# PCB_TX.net
KiCad netlist of a schematic drawn in Altium Designer
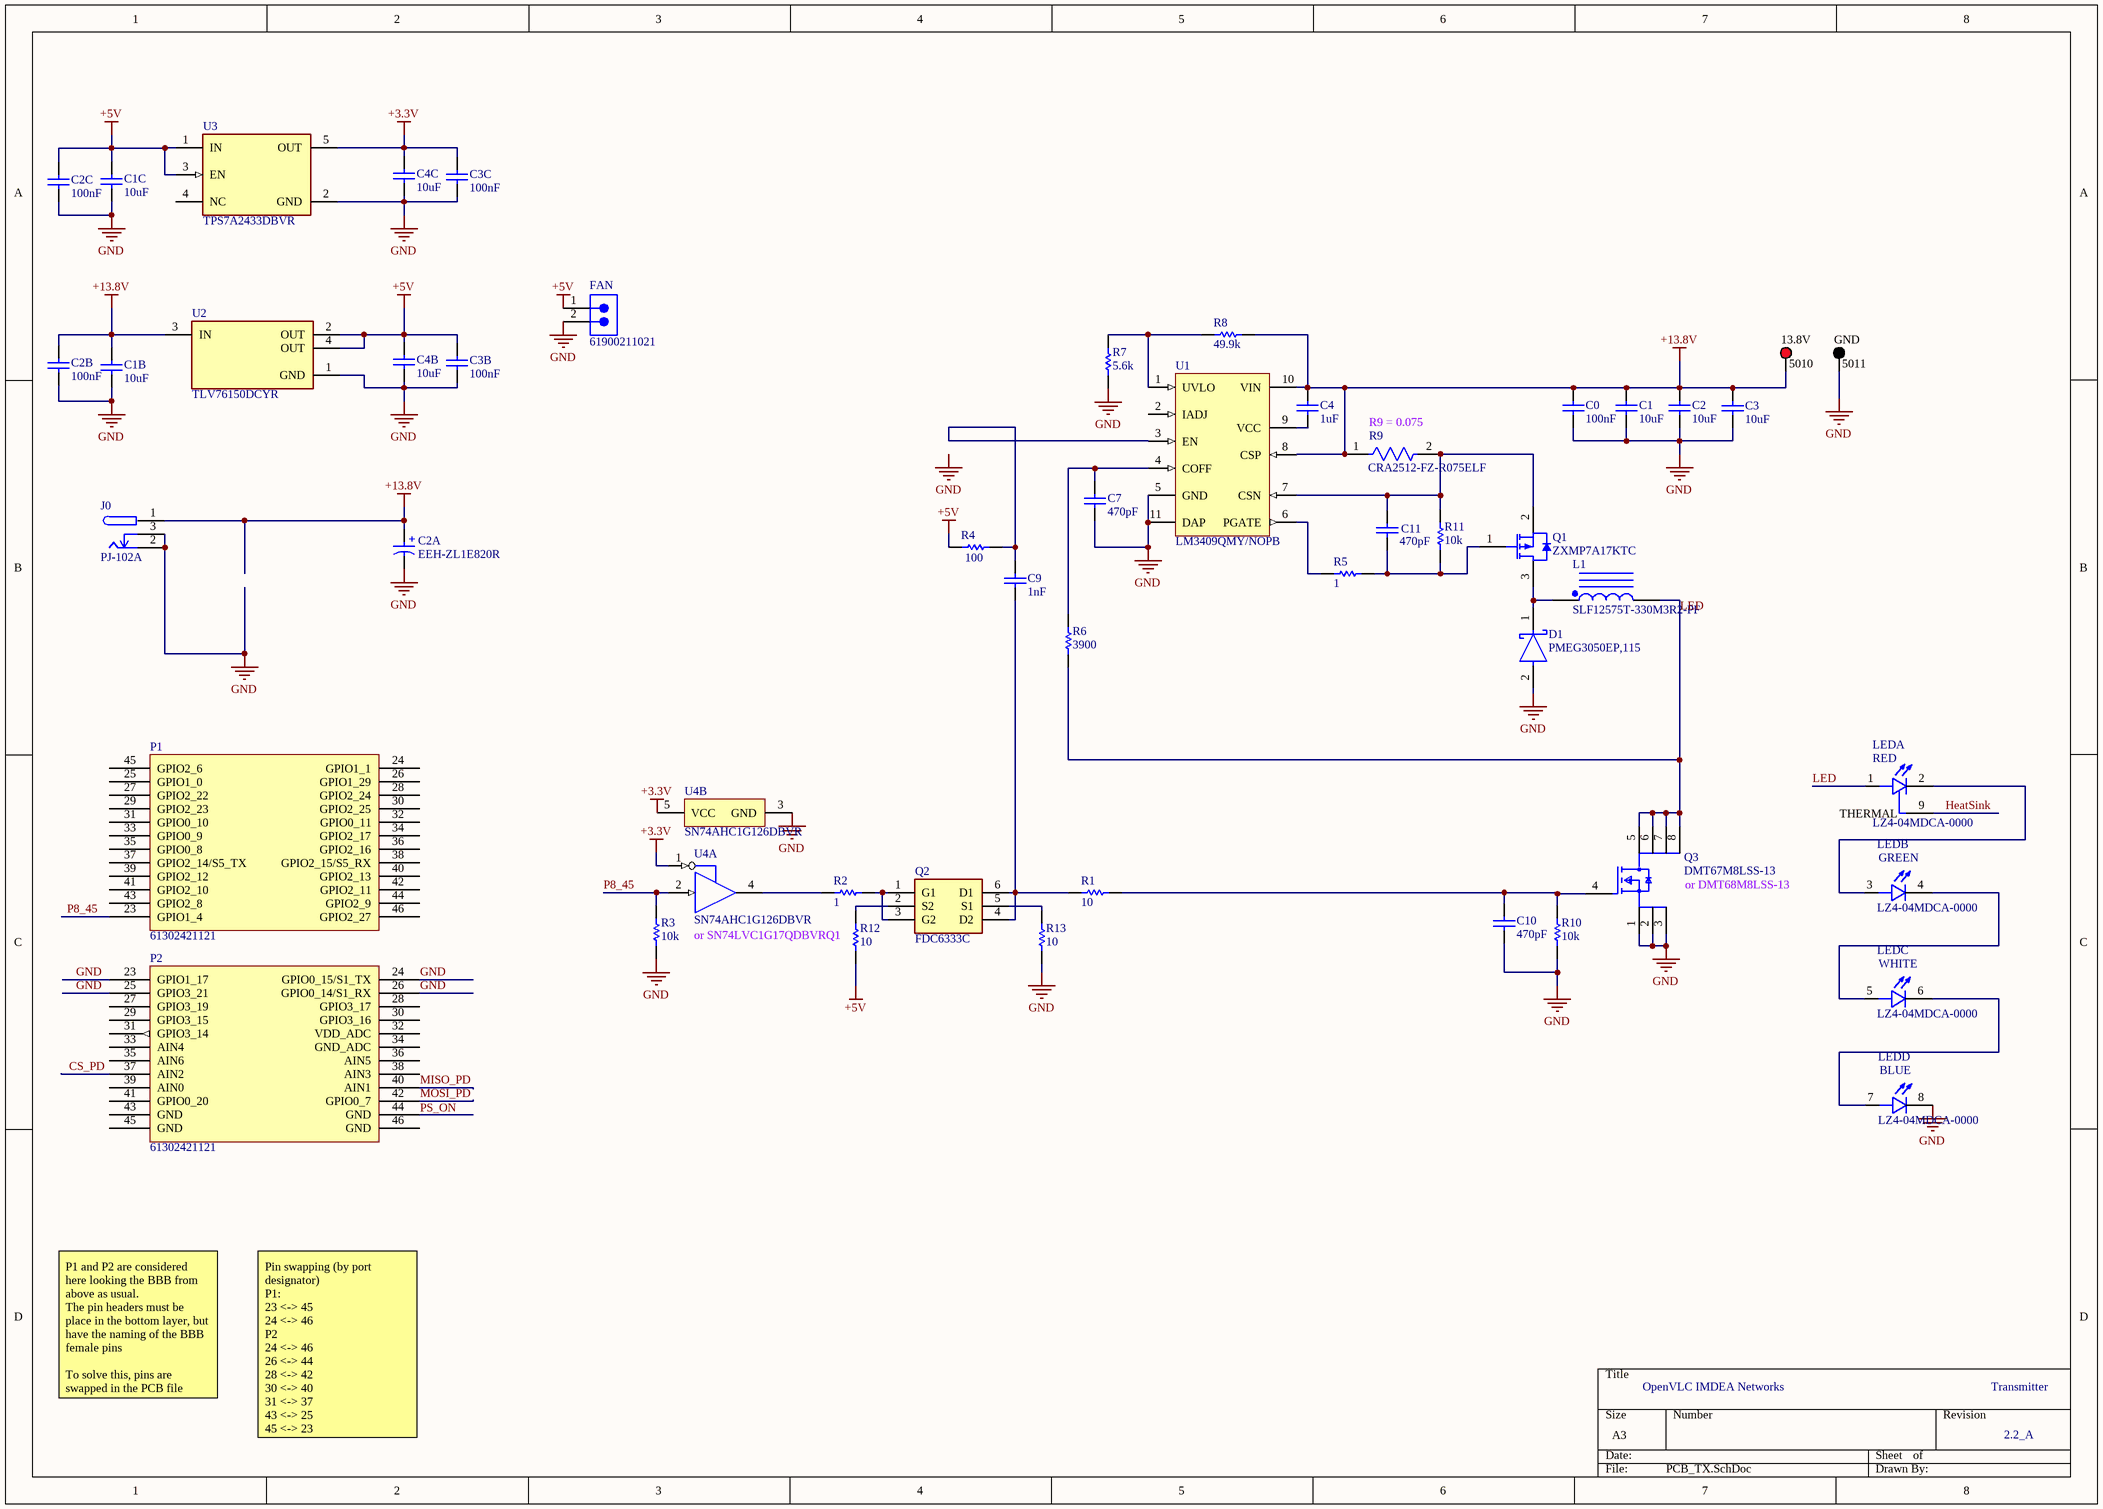
[diagram p0: PCB_TX.SchDoc]

(export (version "E")
  (design (tool "Eeschema 10.0.6"))
  (components
    (comp (ref "13.8V")
      (value "5010")
      (footprint "KSTN-5010_V")
      (description "Test Point, Red, Through Hole, RoHS, Bulk")
      (fields (field (name "MANUFACTURER") "Keystone"))
      (libsource (lib "Altium Content Vault") (part "TESTPOINT_RED"))
    )
    (comp (ref "C0")
      (value "100nF")
      (footprint "RESC1608X55N")
      (description "Capacitor")
      (fields (field (name "Comment") "GCM188R71H104KA57J") (field (name "PUBLISHER") "Altium Limited"))
      (libsource (lib "Miscellaneous Devices") (part "Cap"))
    )
    (comp (ref "C1")
      (value "10uF")
      (footprint "RESC1608X55N")
      (description "Capacitor")
      (fields (field (name "Comment") "GRM188R6YA106MA73D") (field (name "PUBLISHER") "Altium Limited"))
      (libsource (lib "Miscellaneous Devices") (part "Cap"))
    )
    (comp (ref "C1B")
      (value "10uF")
      (footprint "RESC1608X55N")
      (description "Capacitor")
      (fields (field (name "Comment") "GRM188R6YA475KE15D") (field (name "PUBLISHER") "Altium Limited"))
      (libsource (lib "Miscellaneous Devices") (part "Cap"))
    )
    (comp (ref "C1C")
      (value "10uF")
      (footprint "RESC1608X55N")
      (description "Capacitor")
      (fields (field (name "Comment") "GRM188R6YA475KE15D") (field (name "PUBLISHER") "Altium Limited"))
      (libsource (lib "Miscellaneous Devices") (part "Cap"))
    )
    (comp (ref "C2")
      (value "10uF")
      (footprint "RESC1608X55N")
      (description "Capacitor")
      (fields (field (name "Comment") "GRM188R6YA106MA73D") (field (name "PUBLISHER") "Altium Limited"))
      (libsource (lib "Miscellaneous Devices") (part "Cap"))
    )
    (comp (ref "C2A")
      (value "EEH-ZL1E820R")
      (footprint "WCAP-PSLP_D5H5.5")
      (description "875105242006 WCAP-PSLP Aluminum Polymer Capacitors")
      (fields (field (name "TOLERANCE") "20%"))
      (libsource (lib "Altium Content Vault") (part "Capacitor_Polarized"))
    )
    (comp (ref "C2B")
      (value "100nF")
      (footprint "RESC1608X55N")
      (description "Capacitor")
      (fields (field (name "Comment") "GRM188R6YA106MA73D") (field (name "PUBLISHER") "Altium Limited"))
      (libsource (lib "Miscellaneous Devices") (part "Cap"))
    )
    (comp (ref "C2C")
      (value "100nF")
      (footprint "RESC1608X55N")
      (description "Capacitor")
      (fields (field (name "Comment") "GRM188R6YA106MA73D") (field (name "PUBLISHER") "Altium Limited"))
      (libsource (lib "Miscellaneous Devices") (part "Cap"))
    )
    (comp (ref "C3")
      (value "10uF")
      (footprint "RESC1608X55N")
      (description "Capacitor")
      (fields (field (name "Comment") "GRM188R6YA106MA73D") (field (name "PUBLISHER") "Altium Limited"))
      (libsource (lib "Miscellaneous Devices") (part "Cap"))
    )
    (comp (ref "C3B")
      (value "100nF")
      (footprint "RESC1608X55N")
      (description "Capacitor")
      (fields (field (name "Comment") "GCM188R71H104KA57J") (field (name "PUBLISHER") "Altium Limited"))
      (libsource (lib "Miscellaneous Devices") (part "Cap"))
    )
    (comp (ref "C3C")
      (value "100nF")
      (footprint "RESC1608X55N")
      (description "Capacitor")
      (fields (field (name "Comment") "GCM188R71H104KA57J") (field (name "PUBLISHER") "Altium Limited"))
      (libsource (lib "Miscellaneous Devices") (part "Cap"))
    )
    (comp (ref "C4")
      (value "1uF")
      (footprint "RESC1608X55N")
      (description "Capacitor")
      (fields (field (name "Comment") "GCM188D71H105KE36J") (field (name "PUBLISHER") "Altium Limited"))
      (libsource (lib "Miscellaneous Devices") (part "Cap"))
    )
    (comp (ref "C4B")
      (value "10uF")
      (footprint "RESC1608X55N")
      (description "Capacitor")
      (fields (field (name "Comment") "GRM188R6YA106MA73D") (field (name "PUBLISHER") "Altium Limited"))
      (libsource (lib "Miscellaneous Devices") (part "Cap"))
    )
    (comp (ref "C4C")
      (value "10uF")
      (footprint "RESC1608X55N")
      (description "Capacitor")
      (fields (field (name "Comment") "GRM188R6YA106MA73D") (field (name "PUBLISHER") "Altium Limited"))
      (libsource (lib "Miscellaneous Devices") (part "Cap"))
    )
    (comp (ref "C7")
      (value "470pF")
      (footprint "RESC1608X55N")
      (description "Capacitor")
      (fields (field (name "Comment") "GCM1885C1H471JA16D") (field (name "PUBLISHER") "Altium Limited"))
      (libsource (lib "Miscellaneous Devices") (part "Cap"))
    )
    (comp (ref "C9")
      (value "1nF")
      (footprint "RESC1608X55N")
      (description "Capacitor")
      (fields (field (name "Comment") "GRM1885C1H102JA01D") (field (name "PUBLISHER") "Altium Limited"))
      (libsource (lib "Miscellaneous Devices") (part "Cap"))
    )
    (comp (ref "C10")
      (value "470pF")
      (footprint "RESC1608X55N")
      (description "Capacitor")
      (fields (field (name "Comment") "GCM1885C1H471JA16D") (field (name "PUBLISHER") "Altium Limited"))
      (libsource (lib "Miscellaneous Devices") (part "Cap"))
    )
    (comp (ref "C11")
      (value "470pF")
      (footprint "RESC1608X55N")
      (description "Capacitor")
      (fields (field (name "Comment") "GCM1885C1H471JA16D") (field (name "PUBLISHER") "Altium Limited"))
      (libsource (lib "Miscellaneous Devices") (part "Cap"))
    )
    (comp (ref "D1")
      (value "PMEG3050EP,115")
      (footprint "FP-SOD128-MFG")
      (description "DIODE SCHOTTKY 30V 5A SOD128")
      (libsource (lib "Altium Content Vault") (part "1d6ec82d83fb6aee721767c19dac4b9"))
    )
    (comp (ref "FAN")
      (value "61900211021")
      (footprint "61900211021")
      (libsource (lib "Altium Content Vault") (part "Header_Male_1R_02P"))
    )
    (comp (ref "GND")
      (value "5011")
      (footprint "KSTN-5011_V")
      (description "Test Point, Black, Through Hole, RoHS, Bulk")
      (fields (field (name "MANUFACTURER") "Keystone"))
      (libsource (lib "Altium Content Vault") (part "TESTPOINT_BLACK"))
    )
    (comp (ref "J0")
      (value "PJ-102A")
      (footprint "FP-PJ-102A-MFG")
      (description "PJ-102A 2.0 x 6.5 mm, 2.5 A, Horizontal, Through Hole, Tapered Pins, Dc Power Jack Connector")
      (libsource (lib "Altium Content Vault") (part "c639f672d24b5d70918fa8d934b95d1"))
    )
    (comp (ref "L1")
      (value "SLF12575T-330M3R2-PF")
      (footprint "EATN-DR125_V")
      (fields (field (name "MANUFACTURER") "EATON"))
      (libsource (lib "Altium Content Vault") (part "IND-DOT-2"))
    )
    (comp (ref "LED")
      (value "LZ4-04MDCA-0000")
      (footprint "LED_LZ4-04MDCA-0000")
      (fields (field (name "MF") "LED Engin"))
      (libsource (lib "LZ4-04MDCA-0000") (part "LZ4-04MDCA-0000"))
    )
    (comp (ref "P1")
      (value "61302421121")
      (footprint "BBB_CAPE_NO_HEADER_R_24")
      (libsource (lib "BeagleBoneCape") (part "BBB_P8_reduced"))
    )
    (comp (ref "P2")
      (value "61302421121")
      (footprint "BBB_CAPE_NO_HEADER_R_24")
      (libsource (lib "BeagleBoneCape") (part "BBB_P9_reduced"))
    )
    (comp (ref "Q1")
      (value "ZXMP7A17KTC")
      (footprint "DIOD-TO252-3_V")
      (fields (field (name "MANUFACTURER") "Diodes Inc"))
      (libsource (lib "Altium Content Vault") (part "PEMOS-GSD-3"))
    )
    (comp (ref "Q2")
      (value "FDC6333C")
      (footprint "SOT95P275X110-6N")
      (fields (field (name "MOUSER PART NUMBER") "512-FDC6333C"))
      (libsource (lib "FDC6333C") (part "FDC6333C"))
    )
    (comp (ref "Q3")
      (value "DMT67M8LSS-13")
      (footprint "FP-751EB-MFG")
      (description "FDS2672-F085 Trans MOSFET N-CH 200V 3.9A Automotive 8-Pin SOIC T/R")
      (libsource (lib "Altium Content Vault") (part "a2191056e8335feadc5ee6660ea8eee"))
    )
    (comp (ref "R1")
      (value "10")
      (footprint "RESC1608X55N")
      (description "Resistor")
      (fields (field (name "Comment") "RT0603BRD0710RL") (field (name "PUBLISHER") "Altium Limited"))
      (libsource (lib "Miscellaneous Devices") (part "Res1"))
    )
    (comp (ref "R2")
      (value "1")
      (footprint "RESC1608X55N")
      (description "Resistor")
      (fields (field (name "Comment") "RT0603BRD071RL") (field (name "PUBLISHER") "Altium Limited"))
      (libsource (lib "Miscellaneous Devices") (part "Res1"))
    )
    (comp (ref "R3")
      (value "10k")
      (footprint "RESC1608X55N")
      (description "Resistor")
      (fields (field (name "Comment") "RT0603BRD0710KL") (field (name "PUBLISHER") "Altium Limited"))
      (libsource (lib "Miscellaneous Devices") (part "Res1"))
    )
    (comp (ref "R4")
      (value "100")
      (footprint "RESC1608X55N")
      (description "Resistor")
      (fields (field (name "Comment") "RT0603BRD07100RL") (field (name "PUBLISHER") "Altium Limited"))
      (libsource (lib "Miscellaneous Devices") (part "Res1"))
    )
    (comp (ref "R5")
      (value "1")
      (footprint "RESC1608X55N")
      (description "Resistor")
      (fields (field (name "Comment") "RT0603BRD0710RL") (field (name "PUBLISHER") "Altium Limited"))
      (libsource (lib "Miscellaneous Devices") (part "Res1"))
    )
    (comp (ref "R6")
      (value "3900")
      (footprint "RESC1608X55N")
      (description "Resistor")
      (fields (field (name "Comment") "RT0603BRD073K9L") (field (name "PUBLISHER") "Altium Limited"))
      (libsource (lib "Miscellaneous Devices") (part "Res1"))
    )
    (comp (ref "R7")
      (value "5.6k")
      (footprint "RESC1608X55N")
      (description "Resistor")
      (fields (field (name "Comment") "RT0603BRD075K76L") (field (name "PUBLISHER") "Altium Limited"))
      (libsource (lib "Miscellaneous Devices") (part "Res1"))
    )
    (comp (ref "R8")
      (value "49.9k")
      (footprint "RESC1608X55N")
      (description "Resistor")
      (fields (field (name "Comment") "RT0603BRD0749K9L") (field (name "PUBLISHER") "Altium Limited"))
      (libsource (lib "Miscellaneous Devices") (part "Res1"))
    )
    (comp (ref "R9")
      (value "CRA2512-FZ-R075ELF")
      (footprint "FP-CSRN2512-IPC_B")
      (description "Res Thick Film 2512 0.1Ω 1% 2W ±200ppm/°C Molded SMD Plastic T/R")
      (fields (field (name "TOLERANCE") "1%"))
      (libsource (lib "Altium Content Vault") (part "1029c3af85768c4190bb7ad29bc67b5"))
    )
    (comp (ref "R10")
      (value "10k")
      (footprint "RESC1608X55N")
      (description "Resistor")
      (fields (field (name "Comment") "RT0603BRD0710KL") (field (name "PUBLISHER") "Altium Limited"))
      (libsource (lib "Miscellaneous Devices") (part "Res1"))
    )
    (comp (ref "R11")
      (value "10k")
      (footprint "RESC1608X55N")
      (description "Resistor")
      (fields (field (name "Comment") "RT0603BRD0710KL") (field (name "PUBLISHER") "Altium Limited"))
      (libsource (lib "Miscellaneous Devices") (part "Res1"))
    )
    (comp (ref "R12")
      (value "10")
      (footprint "RESC1608X55N")
      (description "Resistor")
      (fields (field (name "Comment") "RT0603BRD0710RL") (field (name "PUBLISHER") "Altium Limited"))
      (libsource (lib "Miscellaneous Devices") (part "Res1"))
    )
    (comp (ref "R13")
      (value "10")
      (footprint "RESC1608X55N")
      (description "Resistor")
      (fields (field (name "Comment") "RT0603BRD0710RL") (field (name "PUBLISHER") "Altium Limited"))
      (libsource (lib "Miscellaneous Devices") (part "Res1"))
    )
    (comp (ref "U1")
      (value "LM3409QMY/NOPB")
      (footprint "DGQ0010A_N")
      (description "PFET Buck Controller for High Power LED Drives, 10-pin eMSOP, Pb-Free")
      (fields (field (name "MANUFACTURER") "Texas Instruments"))
      (libsource (lib "Altium Content Vault") (part "IN-LEDD-LM3409-11"))
    )
    (comp (ref "U2")
      (value "TLV76150DCYR")
      (footprint "FP-DCY0004A-MFG")
      (description "TLV76150DCYR 1-A 16-V high-PSRR linear voltage regulator 4-SOT-223 -40 to 125")
      (libsource (lib "Altium Content Vault") (part "991ffb903c51cf6179ce9942c0606aa"))
    )
    (comp (ref "U3")
      (value "TPS7A2433DBVR")
      (footprint "FP-DBV0005A-MFG")
      (libsource (lib "Altium Content Vault") (part "ee7747973c1ed1d4cccbb20406fa51c"))
    )
    (comp (ref "U4")
      (value "SN74AHC1G126DBVR")
      (footprint "DBV0005A_M")
      (description "Single Bus Buffer Gate With 3-State Outputs, DBV0005A, LARGE T&R")
      (fields
        (field (name "GENERIC PART NUMBER") "SN74AHC1G126")
        (field (name "MANUFACTURER") "Texas Instruments")
      )
      (libsource (lib "Altium Content Vault") (part "TI-SN74XXXXXX126-5"))
    )
  )
  (nets
    (net (code "1") (name "+3.3V") (class "Default")
      (node (ref "C3C") (pin "1") (pinfunction "1_1") (pintype "passive"))
      (node (ref "C4C") (pin "2") (pinfunction "2_2") (pintype "passive"))
      (node (ref "U3") (pin "5") (pinfunction "OUT_5") (pintype "power_in"))
      (node (ref "U4") (pin "1") (pinfunction "OE_1") (pintype "input"))
      (node (ref "U4") (pin "5") (pinfunction "VCC_5") (pintype "power_in"))
    )
    (net (code "2") (name "+5V") (class "Default")
      (node (ref "C1C") (pin "2") (pinfunction "2_2") (pintype "passive"))
      (node (ref "C2C") (pin "1") (pinfunction "1_1") (pintype "passive"))
      (node (ref "C3B") (pin "1") (pinfunction "1_1") (pintype "passive"))
      (node (ref "C4B") (pin "2") (pinfunction "2_2") (pintype "passive"))
      (node (ref "FAN") (pin "1") (pinfunction "1_1") (pintype "passive"))
      (node (ref "R12") (pin "2") (pinfunction "2_2") (pintype "passive"))
      (node (ref "R4") (pin "2") (pinfunction "2_2") (pintype "passive"))
      (node (ref "U2") (pin "2") (pinfunction "OUT_2") (pintype "passive"))
      (node (ref "U2") (pin "4") (pinfunction "OUT_4") (pintype "passive"))
      (node (ref "U3") (pin "1") (pinfunction "IN_1") (pintype "power_in"))
      (node (ref "U3") (pin "3") (pinfunction "EN_3") (pintype "input"))
    )
    (net (code "3") (name "+13.8V") (class "Default")
      (node (ref "13.8V") (pin "1") (pinfunction "1_1") (pintype "passive"))
      (node (ref "C0") (pin "1") (pinfunction "1_1") (pintype "passive"))
      (node (ref "C1") (pin "1") (pinfunction "1_1") (pintype "passive"))
      (node (ref "C1B") (pin "2") (pinfunction "2_2") (pintype "passive"))
      (node (ref "C2") (pin "1") (pinfunction "1_1") (pintype "passive"))
      (node (ref "C2A") (pin "1") (pinfunction "P_1") (pintype "passive"))
      (node (ref "C2B") (pin "1") (pinfunction "1_1") (pintype "passive"))
      (node (ref "C3") (pin "1") (pinfunction "1_1") (pintype "passive"))
      (node (ref "C4") (pin "1") (pinfunction "1_1") (pintype "passive"))
      (node (ref "J0") (pin "1") (pinfunction "1_1") (pintype "passive"))
      (node (ref "R8") (pin "1") (pinfunction "1_1") (pintype "passive"))
      (node (ref "R9") (pin "1") (pinfunction "1_1") (pintype "passive"))
      (node (ref "U1") (pin "10") (pinfunction "VIN_10") (pintype "power_in"))
      (node (ref "U1") (pin "8") (pinfunction "CSP_8") (pintype "input"))
      (node (ref "U2") (pin "3") (pinfunction "IN_3") (pintype "power_in"))
    )
    (net (code "4") (name "/CS_PD") (class "Default")
      (node (ref "P2") (pin "37") (pinfunction "AIN2_37") (pintype "passive"))
    )
    (net (code "5") (name "/HeatSink") (class "Default")
      (node (ref "LED") (pin "9") (pinfunction "THERMAL_9") (pintype "power_in"))
    )
    (net (code "6") (name "/LED") (class "Default")
      (node (ref "L1") (pin "2") (pinfunction "2_2") (pintype "passive"))
      (node (ref "LED") (pin "1") (pinfunction "A_1") (pintype "passive"))
      (node (ref "Q3") (pin "5") (pinfunction "D_5") (pintype "passive"))
      (node (ref "Q3") (pin "6") (pinfunction "D_6") (pintype "passive"))
      (node (ref "Q3") (pin "7") (pinfunction "D_7") (pintype "passive"))
      (node (ref "Q3") (pin "8") (pinfunction "D_8") (pintype "passive"))
      (node (ref "R6") (pin "2") (pinfunction "2_2") (pintype "passive"))
    )
    (net (code "7") (name "/MISO_PD") (class "Default")
      (node (ref "P2") (pin "40") (pinfunction "AIN1_40") (pintype "passive"))
    )
    (net (code "8") (name "/MOSI_PD") (class "Default")
      (node (ref "P2") (pin "42") (pinfunction "GPIO0_7_42") (pintype "passive"))
    )
    (net (code "9") (name "/P8_45") (class "Default")
      (node (ref "P1") (pin "23") (pinfunction "GPIO1_4_23") (pintype "passive"))
      (node (ref "R3") (pin "1") (pinfunction "1_1") (pintype "passive"))
      (node (ref "U4") (pin "2") (pinfunction "A_2") (pintype "input"))
    )
    (net (code "11") (name "GND") (class "Default")
      (node (ref "C0") (pin "2") (pinfunction "2_2") (pintype "passive"))
      (node (ref "C1") (pin "2") (pinfunction "2_2") (pintype "passive"))
      (node (ref "C10") (pin "2") (pinfunction "2_2") (pintype "passive"))
      (node (ref "C1B") (pin "1") (pinfunction "1_1") (pintype "passive"))
      (node (ref "C1C") (pin "1") (pinfunction "1_1") (pintype "passive"))
      (node (ref "C2") (pin "2") (pinfunction "2_2") (pintype "passive"))
      (node (ref "C2A") (pin "2") (pinfunction "N_2") (pintype "passive"))
      (node (ref "C2B") (pin "2") (pinfunction "2_2") (pintype "passive"))
      (node (ref "C2C") (pin "2") (pinfunction "2_2") (pintype "passive"))
      (node (ref "C3") (pin "2") (pinfunction "2_2") (pintype "passive"))
      (node (ref "C3B") (pin "2") (pinfunction "2_2") (pintype "passive"))
      (node (ref "C3C") (pin "2") (pinfunction "2_2") (pintype "passive"))
      (node (ref "C4B") (pin "1") (pinfunction "1_1") (pintype "passive"))
      (node (ref "C4C") (pin "1") (pinfunction "1_1") (pintype "passive"))
      (node (ref "C7") (pin "2") (pinfunction "2_2") (pintype "passive"))
      (node (ref "D1") (pin "2") (pinfunction "A_2") (pintype "passive"))
      (node (ref "FAN") (pin "2") (pinfunction "2_2") (pintype "passive"))
      (node (ref "GND") (pin "1") (pinfunction "1_1") (pintype "passive"))
      (node (ref "J0") (pin "2") (pinfunction "2_2") (pintype "passive"))
      (node (ref "J0") (pin "3") (pinfunction "3_3") (pintype "passive"))
      (node (ref "LED") (pin "8") (pinfunction "C_8") (pintype "passive"))
      (node (ref "P2") (pin "23") (pinfunction "GPIO1_17_23") (pintype "passive"))
      (node (ref "P2") (pin "24") (pinfunction "GPIO0_15/S1_TX_24") (pintype "passive"))
      (node (ref "P2") (pin "25") (pinfunction "GPIO3_21_25") (pintype "passive"))
      (node (ref "P2") (pin "26") (pinfunction "GPIO0_14/S1_RX_26") (pintype "passive"))
      (node (ref "Q3") (pin "1") (pinfunction "S_1") (pintype "passive"))
      (node (ref "Q3") (pin "2") (pinfunction "S_2") (pintype "passive"))
      (node (ref "Q3") (pin "3") (pinfunction "S_3") (pintype "passive"))
      (node (ref "R10") (pin "2") (pinfunction "2_2") (pintype "passive"))
      (node (ref "R13") (pin "2") (pinfunction "2_2") (pintype "passive"))
      (node (ref "R3") (pin "2") (pinfunction "2_2") (pintype "passive"))
      (node (ref "R7") (pin "2") (pinfunction "2_2") (pintype "passive"))
      (node (ref "U1") (pin "11") (pinfunction "DAP_11") (pintype "power_in"))
      (node (ref "U1") (pin "5") (pinfunction "GND_5") (pintype "power_in"))
      (node (ref "U2") (pin "1") (pinfunction "GND_1") (pintype "power_in"))
      (node (ref "U3") (pin "2") (pinfunction "GND_2") (pintype "power_in"))
      (node (ref "U4") (pin "3") (pinfunction "GND_3") (pintype "power_in"))
    )
    (net (code "12") (name "Net-(D1-C)") (class "Default")
      (node (ref "D1") (pin "1") (pinfunction "C_1") (pintype "passive"))
      (node (ref "L1") (pin "1") (pinfunction "1_1") (pintype "passive"))
      (node (ref "Q1") (pin "3") (pinfunction "DRAIN_3") (pintype "passive"))
    )
    (net (code "13") (name "Net-(LEDA-C)") (class "Default")
      (node (ref "LED") (pin "2") (pinfunction "C_2") (pintype "passive"))
      (node (ref "LED") (pin "3") (pinfunction "A_3") (pintype "passive"))
    )
    (net (code "14") (name "Net-(LEDB-C)") (class "Default")
      (node (ref "LED") (pin "4") (pinfunction "C_4") (pintype "passive"))
      (node (ref "LED") (pin "5") (pinfunction "A_5") (pintype "passive"))
    )
    (net (code "15") (name "Net-(LEDC-C)") (class "Default")
      (node (ref "LED") (pin "6") (pinfunction "C_6") (pintype "passive"))
      (node (ref "LED") (pin "7") (pinfunction "A_7") (pintype "passive"))
    )
    (net (code "16") (name "Net-(Q1-GATE)") (class "Default")
      (node (ref "C11") (pin "2") (pinfunction "2_2") (pintype "passive"))
      (node (ref "Q1") (pin "1") (pinfunction "GATE_1") (pintype "passive"))
      (node (ref "R11") (pin "2") (pinfunction "2_2") (pintype "passive"))
      (node (ref "R5") (pin "1") (pinfunction "1_1") (pintype "passive"))
    )
    (net (code "17") (name "Net-(Q1-SOURCE)") (class "Default")
      (node (ref "C11") (pin "1") (pinfunction "1_1") (pintype "passive"))
      (node (ref "Q1") (pin "2") (pinfunction "SOURCE_2") (pintype "passive"))
      (node (ref "R11") (pin "1") (pinfunction "1_1") (pintype "passive"))
      (node (ref "R9") (pin "2") (pinfunction "2_2") (pintype "passive"))
      (node (ref "U1") (pin "7") (pinfunction "CSN_7") (pintype "input"))
    )
    (net (code "18") (name "Net-(Q2-D1)") (class "Default")
      (node (ref "C9") (pin "2") (pinfunction "2_2") (pintype "passive"))
      (node (ref "Q2") (pin "4") (pinfunction "D2_4") (pintype "passive"))
      (node (ref "Q2") (pin "6") (pinfunction "D1_6") (pintype "passive"))
      (node (ref "R1") (pin "2") (pinfunction "2_2") (pintype "passive"))
    )
    (net (code "19") (name "Net-(Q2-G1)") (class "Default")
      (node (ref "Q2") (pin "1") (pinfunction "G1_1") (pintype "passive"))
      (node (ref "Q2") (pin "3") (pinfunction "G2_3") (pintype "passive"))
      (node (ref "R2") (pin "1") (pinfunction "1_1") (pintype "passive"))
    )
    (net (code "20") (name "Net-(Q2-S1)") (class "Default")
      (node (ref "Q2") (pin "5") (pinfunction "S1_5") (pintype "passive"))
      (node (ref "R13") (pin "1") (pinfunction "1_1") (pintype "passive"))
    )
    (net (code "21") (name "Net-(Q2-S2)") (class "Default")
      (node (ref "Q2") (pin "2") (pinfunction "S2_2") (pintype "passive"))
      (node (ref "R12") (pin "1") (pinfunction "1_1") (pintype "passive"))
    )
    (net (code "22") (name "Net-(Q3-G)") (class "Default")
      (node (ref "C10") (pin "1") (pinfunction "1_1") (pintype "passive"))
      (node (ref "Q3") (pin "4") (pinfunction "G_4") (pintype "passive"))
      (node (ref "R1") (pin "1") (pinfunction "1_1") (pintype "passive"))
      (node (ref "R10") (pin "1") (pinfunction "1_1") (pintype "passive"))
    )
    (net (code "23") (name "Net-(U1-COFF)") (class "Default")
      (node (ref "C7") (pin "1") (pinfunction "1_1") (pintype "passive"))
      (node (ref "R6") (pin "1") (pinfunction "1_1") (pintype "passive"))
      (node (ref "U1") (pin "4") (pinfunction "COFF_4") (pintype "input"))
    )
    (net (code "24") (name "Net-(U1-EN)") (class "Default")
      (node (ref "C9") (pin "1") (pinfunction "1_1") (pintype "passive"))
      (node (ref "R4") (pin "1") (pinfunction "1_1") (pintype "passive"))
      (node (ref "U1") (pin "3") (pinfunction "EN_3") (pintype "input"))
    )
    (net (code "25") (name "Net-(U1-PGATE)") (class "Default")
      (node (ref "R5") (pin "2") (pinfunction "2_2") (pintype "passive"))
      (node (ref "U1") (pin "6") (pinfunction "PGATE_6") (pintype "output"))
    )
    (net (code "26") (name "Net-(U1-UVLO)") (class "Default")
      (node (ref "R7") (pin "1") (pinfunction "1_1") (pintype "passive"))
      (node (ref "R8") (pin "2") (pinfunction "2_2") (pintype "passive"))
      (node (ref "U1") (pin "1") (pinfunction "UVLO_1") (pintype "input"))
    )
    (net (code "27") (name "Net-(U1-VCC)") (class "Default")
      (node (ref "C4") (pin "2") (pinfunction "2_2") (pintype "passive"))
      (node (ref "U1") (pin "9") (pinfunction "VCC_9") (pintype "power_in"))
    )
    (net (code "28") (name "Net-(U4A-Y)") (class "Default")
      (node (ref "R2") (pin "2") (pinfunction "2_2") (pintype "passive"))
      (node (ref "U4") (pin "4") (pinfunction "Y_4") (pintype "tri_state"))
    )
    (net (code "29") (name "unconnected-(P1-GPIO0_8-Pad35)") (class "Default")
      (node (ref "P1") (pin "35") (pinfunction "GPIO0_8_35") (pintype "passive"))
    )
    (net (code "30") (name "unconnected-(P1-GPIO0_9-Pad33)") (class "Default")
      (node (ref "P1") (pin "33") (pinfunction "GPIO0_9_33") (pintype "passive"))
    )
    (net (code "31") (name "unconnected-(P1-GPIO0_10-Pad31)") (class "Default")
      (node (ref "P1") (pin "31") (pinfunction "GPIO0_10_31") (pintype "passive"))
    )
    (net (code "32") (name "unconnected-(P1-GPIO0_11-Pad32)") (class "Default")
      (node (ref "P1") (pin "32") (pinfunction "GPIO0_11_32") (pintype "passive"))
    )
    (net (code "33") (name "unconnected-(P1-GPIO1_0-Pad25)") (class "Default")
      (node (ref "P1") (pin "25") (pinfunction "GPIO1_0_25") (pintype "passive"))
    )
    (net (code "34") (name "unconnected-(P1-GPIO1_1-Pad24)") (class "Default")
      (node (ref "P1") (pin "24") (pinfunction "GPIO1_1_24") (pintype "passive"))
    )
    (net (code "35") (name "unconnected-(P1-GPIO1_29-Pad26)") (class "Default")
      (node (ref "P1") (pin "26") (pinfunction "GPIO1_29_26") (pintype "passive"))
    )
    (net (code "36") (name "unconnected-(P1-GPIO2_6-Pad45)") (class "Default")
      (node (ref "P1") (pin "45") (pinfunction "GPIO2_6_45") (pintype "passive"))
    )
    (net (code "37") (name "unconnected-(P1-GPIO2_8-Pad43)") (class "Default")
      (node (ref "P1") (pin "43") (pinfunction "GPIO2_8_43") (pintype "passive"))
    )
    (net (code "38") (name "unconnected-(P1-GPIO2_9-Pad44)") (class "Default")
      (node (ref "P1") (pin "44") (pinfunction "GPIO2_9_44") (pintype "passive"))
    )
    (net (code "39") (name "unconnected-(P1-GPIO2_10-Pad41)") (class "Default")
      (node (ref "P1") (pin "41") (pinfunction "GPIO2_10_41") (pintype "passive"))
    )
    (net (code "40") (name "unconnected-(P1-GPIO2_11-Pad42)") (class "Default")
      (node (ref "P1") (pin "42") (pinfunction "GPIO2_11_42") (pintype "passive"))
    )
    (net (code "41") (name "unconnected-(P1-GPIO2_12-Pad39)") (class "Default")
      (node (ref "P1") (pin "39") (pinfunction "GPIO2_12_39") (pintype "passive"))
    )
    (net (code "42") (name "unconnected-(P1-GPIO2_13-Pad40)") (class "Default")
      (node (ref "P1") (pin "40") (pinfunction "GPIO2_13_40") (pintype "passive"))
    )
    (net (code "43") (name "unconnected-(P1-GPIO2_14{slash}S5_TX-Pad37)") (class "Default")
      (node (ref "P1") (pin "37") (pinfunction "GPIO2_14/S5_TX_37") (pintype "passive"))
    )
    (net (code "44") (name "unconnected-(P1-GPIO2_15{slash}S5_RX-Pad38)") (class "Default")
      (node (ref "P1") (pin "38") (pinfunction "GPIO2_15/S5_RX_38") (pintype "passive"))
    )
    (net (code "45") (name "unconnected-(P1-GPIO2_16-Pad36)") (class "Default")
      (node (ref "P1") (pin "36") (pinfunction "GPIO2_16_36") (pintype "passive"))
    )
    (net (code "46") (name "unconnected-(P1-GPIO2_17-Pad34)") (class "Default")
      (node (ref "P1") (pin "34") (pinfunction "GPIO2_17_34") (pintype "passive"))
    )
    (net (code "47") (name "unconnected-(P1-GPIO2_22-Pad27)") (class "Default")
      (node (ref "P1") (pin "27") (pinfunction "GPIO2_22_27") (pintype "passive"))
    )
    (net (code "48") (name "unconnected-(P1-GPIO2_23-Pad29)") (class "Default")
      (node (ref "P1") (pin "29") (pinfunction "GPIO2_23_29") (pintype "passive"))
    )
    (net (code "49") (name "unconnected-(P1-GPIO2_24-Pad28)") (class "Default")
      (node (ref "P1") (pin "28") (pinfunction "GPIO2_24_28") (pintype "passive"))
    )
    (net (code "50") (name "unconnected-(P1-GPIO2_25-Pad30)") (class "Default")
      (node (ref "P1") (pin "30") (pinfunction "GPIO2_25_30") (pintype "passive"))
    )
    (net (code "51") (name "unconnected-(P1-GPIO2_27-Pad46)") (class "Default")
      (node (ref "P1") (pin "46") (pinfunction "GPIO2_27_46") (pintype "passive"))
    )
    (net (code "52") (name "unconnected-(P2-AIN0-Pad39)") (class "Default")
      (node (ref "P2") (pin "39") (pinfunction "AIN0_39") (pintype "passive"))
    )
    (net (code "53") (name "unconnected-(P2-AIN3-Pad38)") (class "Default")
      (node (ref "P2") (pin "38") (pinfunction "AIN3_38") (pintype "passive"))
    )
    (net (code "54") (name "unconnected-(P2-AIN4-Pad33)") (class "Default")
      (node (ref "P2") (pin "33") (pinfunction "AIN4_33") (pintype "passive"))
    )
    (net (code "55") (name "unconnected-(P2-AIN5-Pad36)") (class "Default")
      (node (ref "P2") (pin "36") (pinfunction "AIN5_36") (pintype "passive"))
    )
    (net (code "56") (name "unconnected-(P2-AIN6-Pad35)") (class "Default")
      (node (ref "P2") (pin "35") (pinfunction "AIN6_35") (pintype "passive"))
    )
    (net (code "57") (name "unconnected-(P2-GND-Pad43)") (class "Default")
      (node (ref "P2") (pin "43") (pinfunction "GND_43") (pintype "passive"))
    )
    (net (code "58") (name "unconnected-(P2-GND-Pad44)") (class "Default")
      (node (ref "P2") (pin "44") (pinfunction "GND_44") (pintype "passive"))
    )
    (net (code "59") (name "unconnected-(P2-GND-Pad45)") (class "Default")
      (node (ref "P2") (pin "45") (pinfunction "GND_45") (pintype "passive"))
    )
    (net (code "60") (name "unconnected-(P2-GND-Pad46)") (class "Default")
      (node (ref "P2") (pin "46") (pinfunction "GND_46") (pintype "passive"))
    )
    (net (code "61") (name "unconnected-(P2-GND_ADC-Pad34)") (class "Default")
      (node (ref "P2") (pin "34") (pinfunction "GND_ADC_34") (pintype "passive"))
    )
    (net (code "62") (name "unconnected-(P2-GPIO0_20-Pad41)") (class "Default")
      (node (ref "P2") (pin "41") (pinfunction "GPIO0_20_41") (pintype "passive"))
    )
    (net (code "63") (name "unconnected-(P2-GPIO3_14-Pad31)") (class "Default")
      (node (ref "P2") (pin "31") (pinfunction "GPIO3_14_31") (pintype "output"))
    )
    (net (code "64") (name "unconnected-(P2-GPIO3_15-Pad29)") (class "Default")
      (node (ref "P2") (pin "29") (pinfunction "GPIO3_15_29") (pintype "passive"))
    )
    (net (code "65") (name "unconnected-(P2-GPIO3_16-Pad30)") (class "Default")
      (node (ref "P2") (pin "30") (pinfunction "GPIO3_16_30") (pintype "passive"))
    )
    (net (code "66") (name "unconnected-(P2-GPIO3_17-Pad28)") (class "Default")
      (node (ref "P2") (pin "28") (pinfunction "GPIO3_17_28") (pintype "passive"))
    )
    (net (code "67") (name "unconnected-(P2-GPIO3_19-Pad27)") (class "Default")
      (node (ref "P2") (pin "27") (pinfunction "GPIO3_19_27") (pintype "passive"))
    )
    (net (code "68") (name "unconnected-(P2-VDD_ADC-Pad32)") (class "Default")
      (node (ref "P2") (pin "32") (pinfunction "VDD_ADC_32") (pintype "passive"))
    )
    (net (code "69") (name "unconnected-(U1-IADJ-Pad2)") (class "Default")
      (node (ref "U1") (pin "2") (pinfunction "IADJ_2") (pintype "input"))
    )
    (net (code "70") (name "unconnected-(U3-NC-Pad4)") (class "Default")
      (node (ref "U3") (pin "4") (pinfunction "NC_4") (pintype "passive"))
    )
  )
)
